# meteostancia_RX.net
KiCad netlist of a schematic drawn in Altium Designer
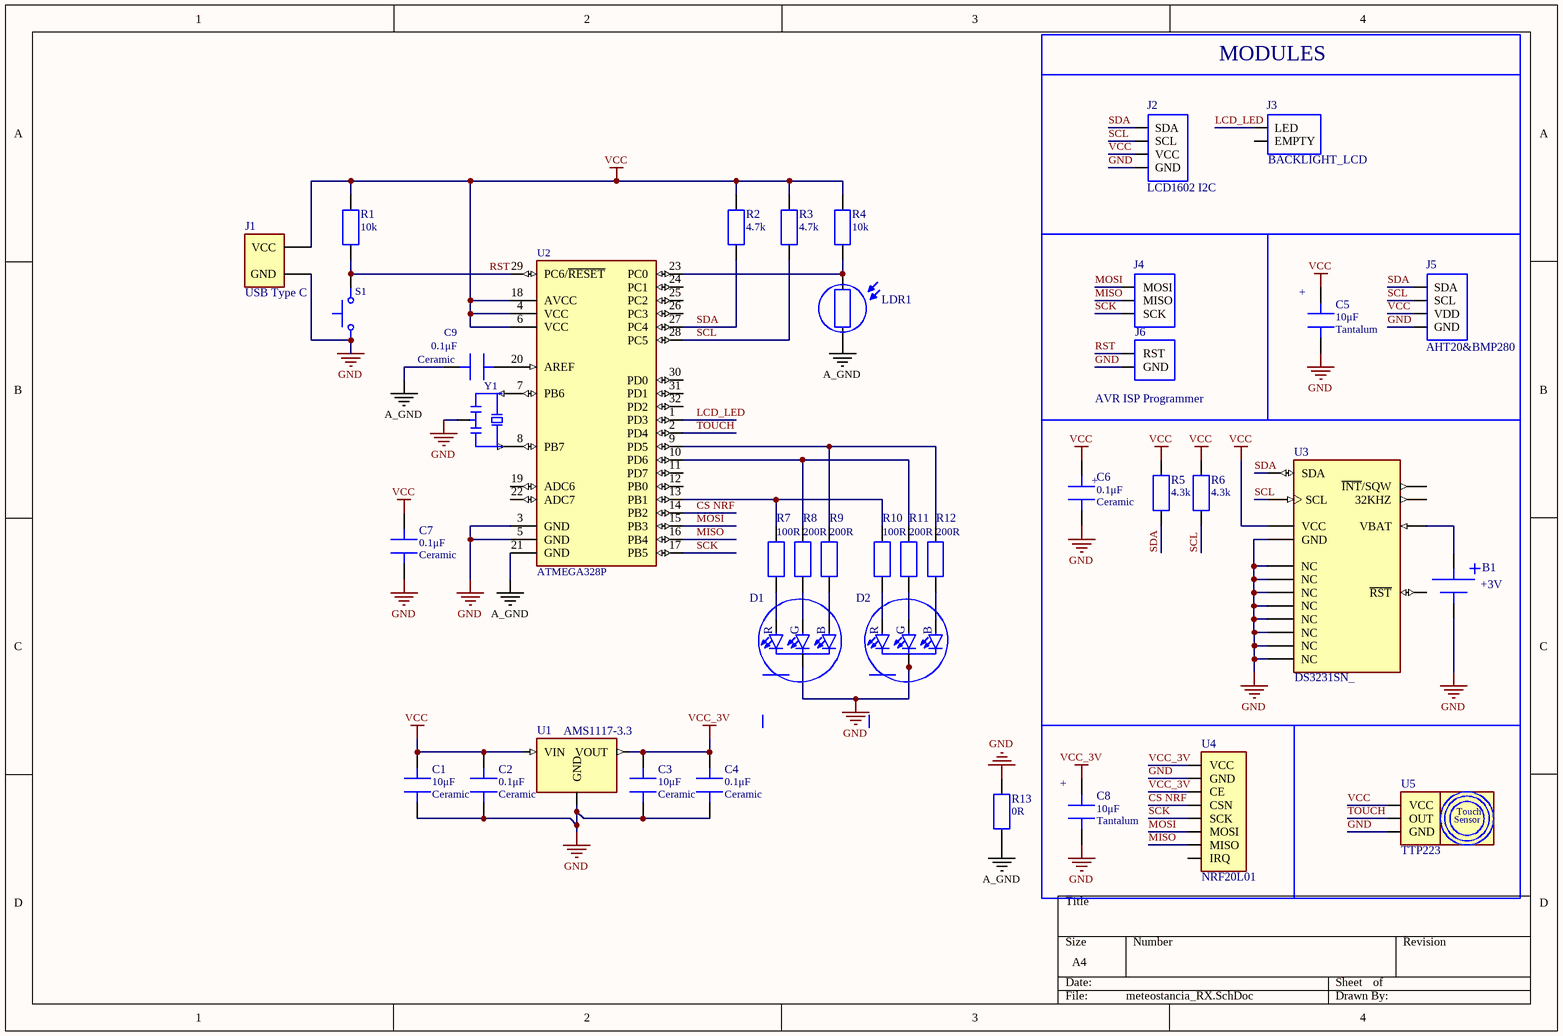
[diagram p0: meteostancia_RX.SchDoc]

(export (version "E")
  (design (tool "Eeschema 10.0.6"))
  (components
    (comp (ref "B1") (value "+3V") (footprint "3V Batery") (libsource (lib "My") (part "Baterry 18650")))
    (comp (ref "C1")
      (value "10μF")
      (footprint "0805")
      (fields (field (name "TYPES") "Ceramic") (field (name "Comment") "Capicator"))
      (libsource (lib "My") (part "Capicator"))
    )
    (comp (ref "C2")
      (value "0.1μF")
      (footprint "0805")
      (fields (field (name "TYPES") "Ceramic") (field (name "Comment") "Capicator"))
      (libsource (lib "My") (part "Capicator"))
    )
    (comp (ref "C3")
      (value "10μF")
      (footprint "0805")
      (fields (field (name "TYPES") "Ceramic") (field (name "Comment") "Capicator"))
      (libsource (lib "My") (part "Capicator"))
    )
    (comp (ref "C4")
      (value "0.1μF")
      (footprint "0805")
      (fields (field (name "TYPES") "Ceramic") (field (name "Comment") "Capicator"))
      (libsource (lib "My") (part "Capicator"))
    )
    (comp (ref "C5")
      (value "10μF")
      (footprint "Capicator 293D size A")
      (fields
        (field (name "POLARITY") "+")
        (field (name "TYPES") "Tantalum")
        (field (name "Comment") "Capicator")
      )
      (libsource (lib "My") (part "Capicator"))
    )
    (comp (ref "C6")
      (value "0.1μF")
      (footprint "0805")
      (fields
        (field (name "POLARITY") "+")
        (field (name "TYPES") "Ceramic")
        (field (name "Comment") "Capicator")
      )
      (libsource (lib "My") (part "Capicator"))
    )
    (comp (ref "C7")
      (value "0.1μF")
      (footprint "0603")
      (fields (field (name "TYPES") "Ceramic") (field (name "Comment") "Capicator"))
      (libsource (lib "My") (part "Capicator"))
    )
    (comp (ref "C8")
      (value "10μF")
      (footprint "Capicator 293D size A")
      (fields
        (field (name "POLARITY") "+")
        (field (name "TYPES") "Tantalum")
        (field (name "Comment") "Capicator")
      )
      (libsource (lib "My") (part "Capicator"))
    )
    (comp (ref "C9")
      (value "0.1μF")
      (footprint "0603")
      (fields (field (name "TYPES") "Ceramic") (field (name "Comment") "Capicator"))
      (libsource (lib "My") (part "Capicator"))
    )
    (comp (ref "D1")
      (value "DIP-LED-RGB")
      (footprint "RGB LED DIP")
      (description "DIP-LED-RGB catode")
      (fields (field (name "MP") "WP7113ID") (field (name "MF") "Kingbright"))
      (libsource (lib "My") (part "DIP-LED-RGB"))
    )
    (comp (ref "D2")
      (value "DIP-LED-RGB")
      (footprint "RGB LED DIP")
      (description "DIP-LED-RGB catode")
      (fields (field (name "MP") "WP7113ID") (field (name "MF") "Kingbright"))
      (libsource (lib "My") (part "DIP-LED-RGB"))
    )
    (comp (ref "J1")
      (value "USB Type C")
      (footprint "18650 PLS 2")
      (description "USB Type C, Power Only, Top mount, Center Height 1.68mm, Single Row, Surface Mount")
      (fields (field (name "MF") "Amphenol") (field (name "MP") "GSB1C411101DSHR"))
      (libsource (lib "My") (part "USB Type C"))
    )
    (comp (ref "J2")
      (value "LCD1602 I2C")
      (footprint "PLS-4 - duplicate")
      (libsource (lib "My") (part "LCD1602 I2C"))
    )
    (comp (ref "J3")
      (value "BACKLIGHT_LCD")
      (footprint "PLS-2")
      (libsource (lib "My") (part "BACKLIGHT_LCD"))
    )
    (comp (ref "J4")
      (value "AVR ISP Programmer")
      (footprint "PLS-3")
      (libsource (lib "My") (part "AVR ISP Programmer"))
    )
    (comp (ref "J5")
      (value "AHT20&BMP280")
      (footprint "AHT20+BMP280")
      (description "High Precision Digital Temperature And Humidity Atmospheric Pressure Sensor")
      (fields (field (name "MF") "Estardyn") (field (name "MP") "AHT20+BMP280"))
      (libsource (lib "My") (part "AHT20+BMP280"))
    )
    (comp (ref "J6")
      (value "AVR ISP Programmer2")
      (footprint "PLS-2")
      (libsource (lib "My") (part "AVR ISP Programmer2"))
    )
    (comp (ref "LDR1")
      (value "photoresistor")
      (footprint "PLS-2")
      (libsource (lib "My") (part "Photoresistor"))
    )
    (comp (ref "R1")
      (value "10k")
      (footprint "R1206")
      (fields (field (name "Comment") "Resistor 1206"))
      (libsource (lib "My") (part "R1206"))
    )
    (comp (ref "R2")
      (value "4.7k")
      (footprint "R1206")
      (fields (field (name "Comment") "Resistor 1206"))
      (libsource (lib "My") (part "R1206"))
    )
    (comp (ref "R3")
      (value "4.7k")
      (footprint "R1206")
      (fields (field (name "Comment") "Resistor 1206"))
      (libsource (lib "My") (part "R1206"))
    )
    (comp (ref "R4")
      (value "10k")
      (footprint "R1206")
      (fields (field (name "Comment") "Resistor 1206"))
      (libsource (lib "My") (part "R1206"))
    )
    (comp (ref "R5")
      (value "4.3k")
      (footprint "0805")
      (fields (field (name "Comment") "Resistor 1206"))
      (libsource (lib "My") (part "R1206"))
    )
    (comp (ref "R6")
      (value "4.3k")
      (footprint "0805")
      (fields (field (name "Comment") "Resistor 1206"))
      (libsource (lib "My") (part "R1206"))
    )
    (comp (ref "R7")
      (value "100R")
      (footprint "R1206")
      (fields (field (name "Comment") "Resistor 1206"))
      (libsource (lib "My") (part "R1206"))
    )
    (comp (ref "R8")
      (value "200R")
      (footprint "R1206")
      (fields (field (name "Comment") "Resistor 1206"))
      (libsource (lib "My") (part "R1206"))
    )
    (comp (ref "R9")
      (value "200R")
      (footprint "R1206")
      (fields (field (name "Comment") "Resistor 1206"))
      (libsource (lib "My") (part "R1206"))
    )
    (comp (ref "R10")
      (value "100R")
      (footprint "R1206")
      (fields (field (name "Comment") "Resistor 1206"))
      (libsource (lib "My") (part "R1206"))
    )
    (comp (ref "R11")
      (value "200R")
      (footprint "R1206")
      (fields (field (name "Comment") "Resistor 1206"))
      (libsource (lib "My") (part "R1206"))
    )
    (comp (ref "R12")
      (value "200R")
      (footprint "R1206")
      (fields (field (name "Comment") "Resistor 1206"))
      (libsource (lib "My") (part "R1206"))
    )
    (comp (ref "R13")
      (value "0R")
      (footprint "R1206")
      (fields (field (name "Comment") "Resistor 1206"))
      (libsource (lib "My") (part "R1206"))
    )
    (comp (ref "S1")
      (value "Switch")
      (footprint "Switch arduino")
      (fields (field (name "MP") "TL1105AF160Q"))
      (libsource (lib "My") (part "Switch"))
    )
    (comp (ref "U1")
      (value "AMS1117-3.3")
      (footprint "AMS1117_SOT229")
      (description "Linear Voltage Regulator IC Positive Fixed 1 Output 1A SOT-223-3L")
      (fields (field (name "MF") "UMW"))
      (libsource (lib "My") (part "AMS1117-3.3"))
    )
    (comp (ref "U2")
      (value "ATMEGA328P")
      (footprint "Atmega328")
      (description "AVR AVRÂ® ATmega Microcontroller IC 8-Bit 20MHz 32KB (16K x 16) FLASH 32-TQFP (7x7)")
      (fields (field (name "MF") "Microchip Technology / Atmel") (field (name "MP") "ATMEGA328P-AN"))
      (libsource (lib "My") (part "ATMEGA328P"))
    )
    (comp (ref "U3")
      (value "DS3231SN_")
      (footprint "SOIC_DS3231SN")
      (description "Real Time Clock (RTC) IC Clock/Calendar - IÂ²C, 2-Wire Serial 16-SOIC (0.295, 7.50mm Width)")
      (fields (field (name "MF") "Maxim Integrated") (field (name "MP") "DS3231SN#"))
      (libsource (lib "My") (part "DS3231SN_"))
    )
    (comp (ref "U4") (value "NRF20L01") (footprint "NRF24L01") (libsource (lib "My") (part "NRF20L01")))
    (comp (ref "U5") (value "TTP223") (footprint "PLS-3") (libsource (lib "My") (part "TTP223")))
    (comp (ref "Y1")
      (value "Ceramic Resonator")
      (footprint "Ceramic Resonator")
      (description "16 MHz Ceramic Resonator Built in Capacitor 15 pF Â±0.3% -20Â°C ~ 80Â°C Surface Mount")
      (fields (field (name "MF") "Murata") (field (name "MP") "CSTCE16M0V53-R0-"))
      (libsource (lib "My") (part "Ceramic Resonator"))
    )
  )
  (nets
    (net (code "1") (name "/CS NRF") (class "Default")
      (node (ref "U2") (pin "14") (pinfunction "PB2_14") (pintype "bidirectional"))
      (node (ref "U4") (pin "4") (pinfunction "CSN_4") (pintype "bidirectional"))
    )
    (net (code "2") (name "/LCD_LED") (class "Default")
      (node (ref "J3") (pin "1") (pinfunction "LED_1") (pintype "passive"))
      (node (ref "U2") (pin "1") (pinfunction "PD3_1") (pintype "bidirectional"))
    )
    (net (code "3") (name "/MISO") (class "Default")
      (node (ref "J4") (pin "2") (pinfunction "MISO_2") (pintype "bidirectional"))
      (node (ref "U2") (pin "16") (pinfunction "PB4_16") (pintype "bidirectional"))
      (node (ref "U4") (pin "7") (pinfunction "MISO_7") (pintype "bidirectional"))
    )
    (net (code "4") (name "/MOSI") (class "Default")
      (node (ref "J4") (pin "1") (pinfunction "MOSI_1") (pintype "bidirectional"))
      (node (ref "U2") (pin "15") (pinfunction "PB3_15") (pintype "bidirectional"))
      (node (ref "U4") (pin "6") (pinfunction "MOSI_6") (pintype "bidirectional"))
    )
    (net (code "5") (name "/RST") (class "Default")
      (node (ref "J6") (pin "1") (pinfunction "RST_1") (pintype "bidirectional"))
      (node (ref "R1") (pin "1") (pinfunction "0_1") (pintype "passive"))
      (node (ref "S1") (pin "2") (pinfunction "2_2") (pintype "passive"))
      (node (ref "U2") (pin "29") (pinfunction "PC6/~{RESET}_29") (pintype "bidirectional"))
    )
    (net (code "6") (name "/SCK") (class "Default")
      (node (ref "J4") (pin "3") (pinfunction "SCK_3") (pintype "bidirectional"))
      (node (ref "U2") (pin "17") (pinfunction "PB5_17") (pintype "bidirectional"))
      (node (ref "U4") (pin "5") (pinfunction "SCK_5") (pintype "bidirectional"))
    )
    (net (code "7") (name "/SCL") (class "Default")
      (node (ref "J2") (pin "4") (pinfunction "SCL_4") (pintype "bidirectional"))
      (node (ref "J5") (pin "SCL") (pinfunction "SCL_SCL") (pintype "bidirectional"))
      (node (ref "R3") (pin "1") (pinfunction "0_1") (pintype "passive"))
      (node (ref "R6") (pin "1") (pinfunction "0_1") (pintype "passive"))
      (node (ref "U2") (pin "28") (pinfunction "PC5_28") (pintype "bidirectional"))
      (node (ref "U3") (pin "16") (pinfunction "SCL_16") (pintype "input"))
    )
    (net (code "8") (name "/SDA") (class "Default")
      (node (ref "J2") (pin "3") (pinfunction "SDA_3") (pintype "bidirectional"))
      (node (ref "J5") (pin "SDA") (pinfunction "SDA_SDA") (pintype "bidirectional"))
      (node (ref "R2") (pin "1") (pinfunction "0_1") (pintype "passive"))
      (node (ref "R5") (pin "1") (pinfunction "0_1") (pintype "passive"))
      (node (ref "U2") (pin "27") (pinfunction "PC4_27") (pintype "bidirectional"))
      (node (ref "U3") (pin "15") (pinfunction "SDA_15") (pintype "bidirectional"))
    )
    (net (code "9") (name "/TOUCH") (class "Default")
      (node (ref "U2") (pin "2") (pinfunction "PD4_2") (pintype "bidirectional"))
      (node (ref "U5") (pin "2") (pinfunction "OUT_2") (pintype "bidirectional"))
    )
    (net (code "10") (name "A_GND") (class "Default")
      (node (ref "C9") (pin "2") (pinfunction "2_2") (pintype "passive"))
      (node (ref "LDR1") (pin "1") (pinfunction "0_1") (pintype "passive"))
      (node (ref "R13") (pin "2") (pinfunction "1_2") (pintype "passive"))
      (node (ref "U2") (pin "21") (pinfunction "GND_21") (pintype "power_in"))
    )
    (net (code "11") (name "GND") (class "Default")
      (node (ref "B1") (pin "2") (pinfunction "2_2") (pintype "passive"))
      (node (ref "C1") (pin "1") (pinfunction "1_1") (pintype "passive"))
      (node (ref "C2") (pin "1") (pinfunction "1_1") (pintype "passive"))
      (node (ref "C3") (pin "1") (pinfunction "1_1") (pintype "passive"))
      (node (ref "C4") (pin "1") (pinfunction "1_1") (pintype "passive"))
      (node (ref "C5") (pin "2") (pinfunction "2_2") (pintype "passive"))
      (node (ref "C6") (pin "2") (pinfunction "2_2") (pintype "passive"))
      (node (ref "C7") (pin "2") (pinfunction "2_2") (pintype "passive"))
      (node (ref "C8") (pin "2") (pinfunction "2_2") (pintype "passive"))
      (node (ref "D1") (pin "2") (pinfunction "GND_2") (pintype "passive"))
      (node (ref "D2") (pin "2") (pinfunction "GND_2") (pintype "passive"))
      (node (ref "J1") (pin "2") (pinfunction "GND_2") (pintype "power_in"))
      (node (ref "J2") (pin "1") (pinfunction "GND_1") (pintype "bidirectional"))
      (node (ref "J5") (pin "GND") (pinfunction "GND_GND") (pintype "bidirectional"))
      (node (ref "J6") (pin "2") (pinfunction "GND_2") (pintype "bidirectional"))
      (node (ref "R13") (pin "1") (pinfunction "0_1") (pintype "passive"))
      (node (ref "S1") (pin "1") (pinfunction "1_1") (pintype "passive"))
      (node (ref "U1") (pin "1") (pinfunction "GND_1") (pintype "power_in"))
      (node (ref "U2") (pin "3") (pinfunction "GND_3") (pintype "power_in"))
      (node (ref "U2") (pin "5") (pinfunction "GND_5") (pintype "power_in"))
      (node (ref "U3") (pin "10") (pinfunction "NC_10") (pintype "passive"))
      (node (ref "U3") (pin "11") (pinfunction "NC_11") (pintype "passive"))
      (node (ref "U3") (pin "12") (pinfunction "NC_12") (pintype "passive"))
      (node (ref "U3") (pin "13") (pinfunction "GND_13") (pintype "power_in"))
      (node (ref "U3") (pin "5") (pinfunction "NC_5") (pintype "passive"))
      (node (ref "U3") (pin "6") (pinfunction "NC_6") (pintype "passive"))
      (node (ref "U3") (pin "7") (pinfunction "NC_7") (pintype "passive"))
      (node (ref "U3") (pin "8") (pinfunction "NC_8") (pintype "passive"))
      (node (ref "U3") (pin "9") (pinfunction "NC_9") (pintype "passive"))
      (node (ref "U4") (pin "2") (pinfunction "GND_2") (pintype "bidirectional"))
      (node (ref "U5") (pin "3") (pinfunction "GND_3") (pintype "bidirectional"))
      (node (ref "Y1") (pin "2") (pinfunction "GND_2") (pintype "power_in"))
    )
    (net (code "12") (name "Net-(D1-B)") (class "Default")
      (node (ref "D1") (pin "4") (pinfunction "B_4") (pintype "passive"))
      (node (ref "R9") (pin "1") (pinfunction "0_1") (pintype "passive"))
    )
    (net (code "13") (name "Net-(D1-G)") (class "Default")
      (node (ref "D1") (pin "3") (pinfunction "G_3") (pintype "passive"))
      (node (ref "R8") (pin "1") (pinfunction "0_1") (pintype "passive"))
    )
    (net (code "14") (name "Net-(D1-R)") (class "Default")
      (node (ref "D1") (pin "1") (pinfunction "R_1") (pintype "passive"))
      (node (ref "R7") (pin "1") (pinfunction "0_1") (pintype "passive"))
    )
    (net (code "15") (name "Net-(D2-B)") (class "Default")
      (node (ref "D2") (pin "4") (pinfunction "B_4") (pintype "passive"))
      (node (ref "R12") (pin "1") (pinfunction "0_1") (pintype "passive"))
    )
    (net (code "16") (name "Net-(D2-G)") (class "Default")
      (node (ref "D2") (pin "3") (pinfunction "G_3") (pintype "passive"))
      (node (ref "R11") (pin "1") (pinfunction "0_1") (pintype "passive"))
    )
    (net (code "17") (name "Net-(D2-R)") (class "Default")
      (node (ref "D2") (pin "1") (pinfunction "R_1") (pintype "passive"))
      (node (ref "R10") (pin "1") (pinfunction "0_1") (pintype "passive"))
    )
    (net (code "18") (name "Net-(LDR1-1)") (class "Default")
      (node (ref "LDR1") (pin "2") (pinfunction "1_2") (pintype "passive"))
      (node (ref "R4") (pin "1") (pinfunction "0_1") (pintype "passive"))
      (node (ref "U2") (pin "23") (pinfunction "PC0_23") (pintype "bidirectional"))
    )
    (net (code "19") (name "Net-(R10-1)") (class "Default")
      (node (ref "R10") (pin "2") (pinfunction "1_2") (pintype "passive"))
      (node (ref "R7") (pin "2") (pinfunction "1_2") (pintype "passive"))
      (node (ref "U2") (pin "13") (pinfunction "PB1_13") (pintype "bidirectional"))
    )
    (net (code "20") (name "Net-(R11-1)") (class "Default")
      (node (ref "R11") (pin "2") (pinfunction "1_2") (pintype "passive"))
      (node (ref "R8") (pin "2") (pinfunction "1_2") (pintype "passive"))
      (node (ref "U2") (pin "10") (pinfunction "PD6_10") (pintype "bidirectional"))
    )
    (net (code "21") (name "Net-(R12-1)") (class "Default")
      (node (ref "R12") (pin "2") (pinfunction "1_2") (pintype "passive"))
      (node (ref "R9") (pin "2") (pinfunction "1_2") (pintype "passive"))
      (node (ref "U2") (pin "9") (pinfunction "PD5_9") (pintype "bidirectional"))
    )
    (net (code "22") (name "Net-(U2-AREF)") (class "Default")
      (node (ref "C9") (pin "1") (pinfunction "1_1") (pintype "passive"))
      (node (ref "U2") (pin "20") (pinfunction "AREF_20") (pintype "input"))
    )
    (net (code "23") (name "Net-(U2-PB6)") (class "Default")
      (node (ref "U2") (pin "7") (pinfunction "PB6_7") (pintype "bidirectional"))
      (node (ref "Y1") (pin "1") (pinfunction "IN_1") (pintype "input"))
    )
    (net (code "24") (name "Net-(U2-PB7)") (class "Default")
      (node (ref "U2") (pin "8") (pinfunction "PB7_8") (pintype "bidirectional"))
      (node (ref "Y1") (pin "3") (pinfunction "OUT_3") (pintype "output"))
    )
    (net (code "25") (name "Net-(U3-VBAT)") (class "Default")
      (node (ref "B1") (pin "1") (pinfunction "1_1") (pintype "passive"))
      (node (ref "U3") (pin "14") (pinfunction "VBAT_14") (pintype "input"))
    )
    (net (code "26") (name "VCC") (class "Default")
      (node (ref "C1") (pin "2") (pinfunction "2_2") (pintype "passive"))
      (node (ref "C2") (pin "2") (pinfunction "2_2") (pintype "passive"))
      (node (ref "C5") (pin "1") (pinfunction "1_1") (pintype "passive"))
      (node (ref "C6") (pin "1") (pinfunction "1_1") (pintype "passive"))
      (node (ref "C7") (pin "1") (pinfunction "1_1") (pintype "passive"))
      (node (ref "J1") (pin "1") (pinfunction "VCC_1") (pintype "power_in"))
      (node (ref "J2") (pin "2") (pinfunction "VCC_2") (pintype "bidirectional"))
      (node (ref "J5") (pin "VDD") (pinfunction "VDD_VDD") (pintype "bidirectional"))
      (node (ref "R1") (pin "2") (pinfunction "1_2") (pintype "passive"))
      (node (ref "R2") (pin "2") (pinfunction "1_2") (pintype "passive"))
      (node (ref "R3") (pin "2") (pinfunction "1_2") (pintype "passive"))
      (node (ref "R4") (pin "2") (pinfunction "1_2") (pintype "passive"))
      (node (ref "R5") (pin "2") (pinfunction "1_2") (pintype "passive"))
      (node (ref "R6") (pin "2") (pinfunction "1_2") (pintype "passive"))
      (node (ref "U1") (pin "3") (pinfunction "VIN_3") (pintype "input"))
      (node (ref "U2") (pin "18") (pinfunction "AVCC_18") (pintype "power_in"))
      (node (ref "U2") (pin "4") (pinfunction "VCC_4") (pintype "power_in"))
      (node (ref "U2") (pin "6") (pinfunction "VCC_6") (pintype "power_in"))
      (node (ref "U3") (pin "2") (pinfunction "VCC_2") (pintype "power_in"))
      (node (ref "U5") (pin "1") (pinfunction "VCC_1") (pintype "bidirectional"))
    )
    (net (code "27") (name "VCC_3V") (class "Default")
      (node (ref "C3") (pin "2") (pinfunction "2_2") (pintype "passive"))
      (node (ref "C4") (pin "2") (pinfunction "2_2") (pintype "passive"))
      (node (ref "C8") (pin "1") (pinfunction "1_1") (pintype "passive"))
      (node (ref "U1") (pin "2") (pinfunction "VOUT_2") (pintype "output"))
      (node (ref "U4") (pin "1") (pinfunction "VCC_1") (pintype "bidirectional"))
      (node (ref "U4") (pin "3") (pinfunction "CE_3") (pintype "bidirectional"))
    )
    (net (code "28") (name "unconnected-(J3-EMPTY-Pad2)") (class "Default")
      (node (ref "J3") (pin "2") (pinfunction "EMPTY_2") (pintype "passive"))
    )
    (net (code "29") (name "unconnected-(U2-ADC6-Pad19)") (class "Default")
      (node (ref "U2") (pin "19") (pinfunction "ADC6_19") (pintype "bidirectional"))
    )
    (net (code "30") (name "unconnected-(U2-ADC7-Pad22)") (class "Default")
      (node (ref "U2") (pin "22") (pinfunction "ADC7_22") (pintype "bidirectional"))
    )
    (net (code "31") (name "unconnected-(U2-PB0-Pad12)") (class "Default")
      (node (ref "U2") (pin "12") (pinfunction "PB0_12") (pintype "bidirectional"))
    )
    (net (code "32") (name "unconnected-(U2-PC1-Pad24)") (class "Default")
      (node (ref "U2") (pin "24") (pinfunction "PC1_24") (pintype "bidirectional"))
    )
    (net (code "33") (name "unconnected-(U2-PC2-Pad25)") (class "Default")
      (node (ref "U2") (pin "25") (pinfunction "PC2_25") (pintype "bidirectional"))
    )
    (net (code "34") (name "unconnected-(U2-PC3-Pad26)") (class "Default")
      (node (ref "U2") (pin "26") (pinfunction "PC3_26") (pintype "bidirectional"))
    )
    (net (code "35") (name "unconnected-(U2-PD0-Pad30)") (class "Default")
      (node (ref "U2") (pin "30") (pinfunction "PD0_30") (pintype "bidirectional"))
    )
    (net (code "36") (name "unconnected-(U2-PD1-Pad31)") (class "Default")
      (node (ref "U2") (pin "31") (pinfunction "PD1_31") (pintype "bidirectional"))
    )
    (net (code "37") (name "unconnected-(U2-PD2-Pad32)") (class "Default")
      (node (ref "U2") (pin "32") (pinfunction "PD2_32") (pintype "bidirectional"))
    )
    (net (code "38") (name "unconnected-(U2-PD7-Pad11)") (class "Default")
      (node (ref "U2") (pin "11") (pinfunction "PD7_11") (pintype "bidirectional"))
    )
    (net (code "39") (name "unconnected-(U3-32KHZ-Pad1)") (class "Default")
      (node (ref "U3") (pin "1") (pinfunction "32KHZ_1") (pintype "output"))
    )
    (net (code "40") (name "unconnected-(U3-~{INT}{slash}SQW-Pad3)") (class "Default")
      (node (ref "U3") (pin "3") (pinfunction "~{INT}/SQW_3") (pintype "output"))
    )
    (net (code "41") (name "unconnected-(U3-~{RST}-Pad4)") (class "Default")
      (node (ref "U3") (pin "4") (pinfunction "~{RST}_4") (pintype "bidirectional"))
    )
    (net (code "42") (name "unconnected-(U4-IRQ-Pad8)") (class "Default")
      (node (ref "U4") (pin "8") (pinfunction "IRQ_8") (pintype "bidirectional"))
    )
  )
)
